# YOTSUBA_AP-ex_EM_ver_3_1.net
KiCad netlist of a schematic drawn in EAGLE
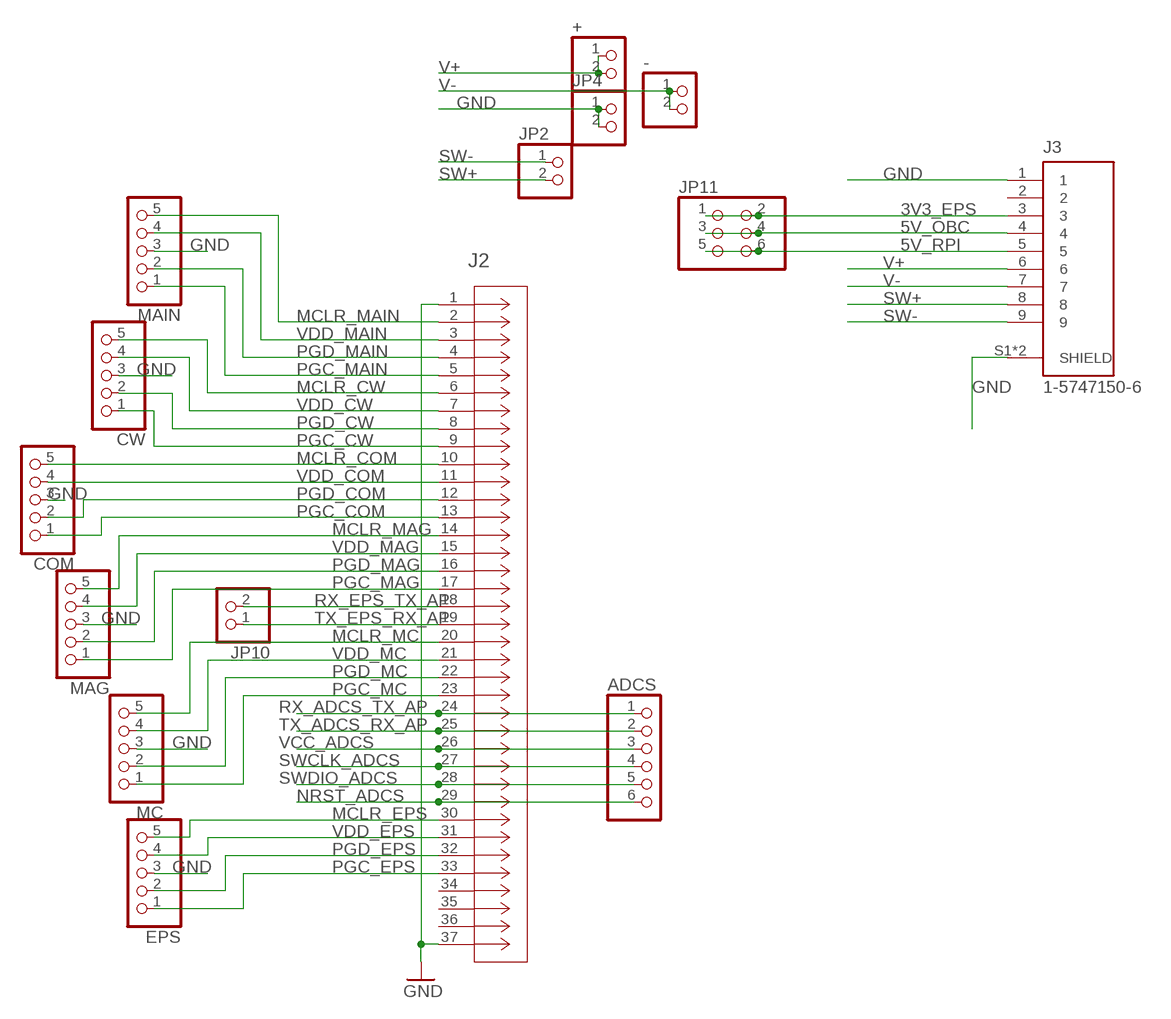
[diagram p0: schematic, sheet 1]

(export (version "E")
  (design (tool "Eeschema 10.0.6"))
  (components
    (comp (ref "+")
      (value "PINHD-1X2")
      (footprint "eagle-import:1X02")
      (libsource (lib "eagle-import") (part "PINHD-1X2"))
    )
    (comp (ref "-")
      (value "PINHD-1X2")
      (footprint "eagle-import:1X02")
      (libsource (lib "eagle-import") (part "PINHD-1X2"))
    )
    (comp (ref "ADCS")
      (value "PINHD-1X6")
      (footprint "eagle-import:1X06")
      (libsource (lib "eagle-import") (part "PINHD-1X6"))
    )
    (comp (ref "COM")
      (value "PINHD-1X5")
      (footprint "eagle-import:1X05")
      (libsource (lib "eagle-import") (part "PINHD-1X5"))
    )
    (comp (ref "CW")
      (value "PINHD-1X5")
      (footprint "eagle-import:1X05")
      (libsource (lib "eagle-import") (part "PINHD-1X5"))
    )
    (comp (ref "EPS")
      (value "PINHD-1X5")
      (footprint "eagle-import:1X05")
      (libsource (lib "eagle-import") (part "PINHD-1X5"))
    )
    (comp (ref "J2")
      (value "1-5747301-6")
      (footprint "eagle-import:CONN_1-5747301-6_TYC")
      (fields (field (name "COPYRIGHT") "Copyright (C) 2023 Ultra Librarian. All rights reserved."))
      (libsource (lib "eagle-import") (part "1-5747301-6"))
    )
    (comp (ref "J3")
      (value "1-5747150-6")
      (footprint "eagle-import:TE_1-5747150-6")
      (fields (field (name "MF") "TE Connectivity"))
      (libsource (lib "eagle-import") (part "1-5747150-6"))
    )
    (comp (ref "JP2")
      (value "PINHD-1X2")
      (footprint "eagle-import:1X02")
      (libsource (lib "eagle-import") (part "PINHD-1X2"))
    )
    (comp (ref "JP4")
      (value "PINHD-1X2")
      (footprint "eagle-import:1X02")
      (libsource (lib "eagle-import") (part "PINHD-1X2"))
    )
    (comp (ref "JP10")
      (value "PINHD-1X2")
      (footprint "eagle-import:1X02")
      (libsource (lib "eagle-import") (part "PINHD-1X2"))
    )
    (comp (ref "JP11")
      (value "PINHD-2X3")
      (footprint "eagle-import:2X03")
      (libsource (lib "eagle-import") (part "PINHD-2X3"))
    )
    (comp (ref "MAG")
      (value "PINHD-1X5")
      (footprint "eagle-import:1X05")
      (libsource (lib "eagle-import") (part "PINHD-1X5"))
    )
    (comp (ref "MAIN")
      (value "PINHD-1X5")
      (footprint "eagle-import:1X05")
      (libsource (lib "eagle-import") (part "PINHD-1X5"))
    )
    (comp (ref "MC")
      (value "PINHD-1X5")
      (footprint "eagle-import:1X05")
      (libsource (lib "eagle-import") (part "PINHD-1X5"))
    )
  )
  (nets
    (net (code "1") (name "/3V3_EPS") (class "Default")
      (node (ref "J3") (pin "3") (pinfunction "3_3") (pintype "passive"))
      (node (ref "JP11") (pin "1") (pinfunction "1_1") (pintype "passive"))
      (node (ref "JP11") (pin "2") (pinfunction "2_2") (pintype "passive"))
    )
    (net (code "2") (name "/5V_OBC") (class "Default")
      (node (ref "J3") (pin "4") (pinfunction "4_4") (pintype "passive"))
      (node (ref "JP11") (pin "3") (pinfunction "3_3") (pintype "passive"))
      (node (ref "JP11") (pin "4") (pinfunction "4_4") (pintype "passive"))
    )
    (net (code "3") (name "/5V_RPI") (class "Default")
      (node (ref "J3") (pin "5") (pinfunction "5_5") (pintype "passive"))
      (node (ref "JP11") (pin "5") (pinfunction "5_5") (pintype "passive"))
      (node (ref "JP11") (pin "6") (pinfunction "6_6") (pintype "passive"))
    )
    (net (code "4") (name "/MCLR_COM") (class "Default")
      (node (ref "COM") (pin "5") (pinfunction "5_5") (pintype "passive"))
      (node (ref "J2") (pin "10") (pinfunction "10_10") (pintype "passive"))
    )
    (net (code "5") (name "/MCLR_CW") (class "Default")
      (node (ref "CW") (pin "5") (pinfunction "5_5") (pintype "passive"))
      (node (ref "J2") (pin "6") (pinfunction "6_6") (pintype "passive"))
    )
    (net (code "6") (name "/MCLR_EPS") (class "Default")
      (node (ref "EPS") (pin "5") (pinfunction "5_5") (pintype "passive"))
      (node (ref "J2") (pin "30") (pinfunction "30_30") (pintype "passive"))
    )
    (net (code "7") (name "/MCLR_MAG") (class "Default")
      (node (ref "J2") (pin "14") (pinfunction "14_14") (pintype "passive"))
      (node (ref "MAG") (pin "5") (pinfunction "5_5") (pintype "passive"))
    )
    (net (code "8") (name "/MCLR_MAIN") (class "Default")
      (node (ref "J2") (pin "2") (pinfunction "2_2") (pintype "passive"))
      (node (ref "MAIN") (pin "5") (pinfunction "5_5") (pintype "passive"))
    )
    (net (code "9") (name "/MCLR_MC") (class "Default")
      (node (ref "J2") (pin "20") (pinfunction "20_20") (pintype "passive"))
      (node (ref "MC") (pin "5") (pinfunction "5_5") (pintype "passive"))
    )
    (net (code "10") (name "/NRST_ADCS") (class "Default")
      (node (ref "ADCS") (pin "6") (pinfunction "6_6") (pintype "passive"))
      (node (ref "J2") (pin "29") (pinfunction "29_29") (pintype "passive"))
    )
    (net (code "11") (name "/PGC_COM") (class "Default")
      (node (ref "COM") (pin "1") (pinfunction "1_1") (pintype "passive"))
      (node (ref "J2") (pin "13") (pinfunction "13_13") (pintype "passive"))
    )
    (net (code "12") (name "/PGC_CW") (class "Default")
      (node (ref "CW") (pin "1") (pinfunction "1_1") (pintype "passive"))
      (node (ref "J2") (pin "9") (pinfunction "9_9") (pintype "passive"))
    )
    (net (code "13") (name "/PGC_EPS") (class "Default")
      (node (ref "EPS") (pin "1") (pinfunction "1_1") (pintype "passive"))
      (node (ref "J2") (pin "33") (pinfunction "33_33") (pintype "passive"))
    )
    (net (code "14") (name "/PGC_MAG") (class "Default")
      (node (ref "J2") (pin "17") (pinfunction "17_17") (pintype "passive"))
      (node (ref "MAG") (pin "1") (pinfunction "1_1") (pintype "passive"))
    )
    (net (code "15") (name "/PGC_MAIN") (class "Default")
      (node (ref "J2") (pin "5") (pinfunction "5_5") (pintype "passive"))
      (node (ref "MAIN") (pin "1") (pinfunction "1_1") (pintype "passive"))
    )
    (net (code "16") (name "/PGC_MC") (class "Default")
      (node (ref "J2") (pin "23") (pinfunction "23_23") (pintype "passive"))
      (node (ref "MC") (pin "1") (pinfunction "1_1") (pintype "passive"))
    )
    (net (code "17") (name "/PGD_COM") (class "Default")
      (node (ref "COM") (pin "2") (pinfunction "2_2") (pintype "passive"))
      (node (ref "J2") (pin "12") (pinfunction "12_12") (pintype "passive"))
    )
    (net (code "18") (name "/PGD_CW") (class "Default")
      (node (ref "CW") (pin "2") (pinfunction "2_2") (pintype "passive"))
      (node (ref "J2") (pin "8") (pinfunction "8_8") (pintype "passive"))
    )
    (net (code "19") (name "/PGD_EPS") (class "Default")
      (node (ref "EPS") (pin "2") (pinfunction "2_2") (pintype "passive"))
      (node (ref "J2") (pin "32") (pinfunction "32_32") (pintype "passive"))
    )
    (net (code "20") (name "/PGD_MAG") (class "Default")
      (node (ref "J2") (pin "16") (pinfunction "16_16") (pintype "passive"))
      (node (ref "MAG") (pin "2") (pinfunction "2_2") (pintype "passive"))
    )
    (net (code "21") (name "/PGD_MAIN") (class "Default")
      (node (ref "J2") (pin "4") (pinfunction "4_4") (pintype "passive"))
      (node (ref "MAIN") (pin "2") (pinfunction "2_2") (pintype "passive"))
    )
    (net (code "22") (name "/PGD_MC") (class "Default")
      (node (ref "J2") (pin "22") (pinfunction "22_22") (pintype "passive"))
      (node (ref "MC") (pin "2") (pinfunction "2_2") (pintype "passive"))
    )
    (net (code "23") (name "/RX_ADCS_TX_AP") (class "Default")
      (node (ref "ADCS") (pin "1") (pinfunction "1_1") (pintype "passive"))
      (node (ref "J2") (pin "24") (pinfunction "24_24") (pintype "passive"))
    )
    (net (code "24") (name "/RX_EPS_TX_AP") (class "Default")
      (node (ref "J2") (pin "18") (pinfunction "18_18") (pintype "passive"))
      (node (ref "JP10") (pin "2") (pinfunction "2_2") (pintype "passive"))
    )
    (net (code "25") (name "/SW+") (class "Default")
      (node (ref "J3") (pin "8") (pinfunction "8_8") (pintype "passive"))
      (node (ref "JP2") (pin "2") (pinfunction "2_2") (pintype "passive"))
    )
    (net (code "26") (name "/SW-") (class "Default")
      (node (ref "J3") (pin "9") (pinfunction "9_9") (pintype "passive"))
      (node (ref "JP2") (pin "1") (pinfunction "1_1") (pintype "passive"))
    )
    (net (code "27") (name "/SWCLK_ADCS") (class "Default")
      (node (ref "ADCS") (pin "4") (pinfunction "4_4") (pintype "passive"))
      (node (ref "J2") (pin "27") (pinfunction "27_27") (pintype "passive"))
    )
    (net (code "28") (name "/SWDIO_ADCS") (class "Default")
      (node (ref "ADCS") (pin "5") (pinfunction "5_5") (pintype "passive"))
      (node (ref "J2") (pin "28") (pinfunction "28_28") (pintype "passive"))
    )
    (net (code "29") (name "/TX_ADCS_RX_AP") (class "Default")
      (node (ref "ADCS") (pin "2") (pinfunction "2_2") (pintype "passive"))
      (node (ref "J2") (pin "25") (pinfunction "25_25") (pintype "passive"))
    )
    (net (code "30") (name "/TX_EPS_RX_AP") (class "Default")
      (node (ref "J2") (pin "19") (pinfunction "19_19") (pintype "passive"))
      (node (ref "JP10") (pin "1") (pinfunction "1_1") (pintype "passive"))
    )
    (net (code "31") (name "/V+") (class "Default")
      (node (ref "+") (pin "1") (pinfunction "1_1") (pintype "passive"))
      (node (ref "+") (pin "2") (pinfunction "2_2") (pintype "passive"))
      (node (ref "J3") (pin "6") (pinfunction "6_6") (pintype "passive"))
    )
    (net (code "32") (name "/V-") (class "Default")
      (node (ref "-") (pin "1") (pinfunction "1_1") (pintype "passive"))
      (node (ref "-") (pin "2") (pinfunction "2_2") (pintype "passive"))
      (node (ref "J3") (pin "7") (pinfunction "7_7") (pintype "passive"))
    )
    (net (code "33") (name "/VCC_ADCS") (class "Default")
      (node (ref "ADCS") (pin "3") (pinfunction "3_3") (pintype "passive"))
      (node (ref "J2") (pin "26") (pinfunction "26_26") (pintype "passive"))
    )
    (net (code "34") (name "/VDD_COM") (class "Default")
      (node (ref "COM") (pin "4") (pinfunction "4_4") (pintype "passive"))
      (node (ref "J2") (pin "11") (pinfunction "11_11") (pintype "passive"))
    )
    (net (code "35") (name "/VDD_CW") (class "Default")
      (node (ref "CW") (pin "4") (pinfunction "4_4") (pintype "passive"))
      (node (ref "J2") (pin "7") (pinfunction "7_7") (pintype "passive"))
    )
    (net (code "36") (name "/VDD_EPS") (class "Default")
      (node (ref "EPS") (pin "4") (pinfunction "4_4") (pintype "passive"))
      (node (ref "J2") (pin "31") (pinfunction "31_31") (pintype "passive"))
    )
    (net (code "37") (name "/VDD_MAG") (class "Default")
      (node (ref "J2") (pin "15") (pinfunction "15_15") (pintype "passive"))
      (node (ref "MAG") (pin "4") (pinfunction "4_4") (pintype "passive"))
    )
    (net (code "38") (name "/VDD_MAIN") (class "Default")
      (node (ref "J2") (pin "3") (pinfunction "3_3") (pintype "passive"))
      (node (ref "MAIN") (pin "4") (pinfunction "4_4") (pintype "passive"))
    )
    (net (code "39") (name "/VDD_MC") (class "Default")
      (node (ref "J2") (pin "21") (pinfunction "21_21") (pintype "passive"))
      (node (ref "MC") (pin "4") (pinfunction "4_4") (pintype "passive"))
    )
    (net (code "40") (name "GND") (class "Default")
      (node (ref "COM") (pin "3") (pinfunction "3_3") (pintype "passive"))
      (node (ref "CW") (pin "3") (pinfunction "3_3") (pintype "passive"))
      (node (ref "EPS") (pin "3") (pinfunction "3_3") (pintype "passive"))
      (node (ref "J2") (pin "1") (pinfunction "1_1") (pintype "passive"))
      (node (ref "J2") (pin "37") (pinfunction "37_37") (pintype "passive"))
      (node (ref "J3") (pin "1") (pinfunction "1_1") (pintype "passive"))
      (node (ref "J3") (pin "S1") (pinfunction "SHIELD_S1") (pintype "passive"))
      (node (ref "J3") (pin "S2") (pinfunction "SHIELD_S2") (pintype "passive"))
      (node (ref "JP4") (pin "1") (pinfunction "1_1") (pintype "passive"))
      (node (ref "JP4") (pin "2") (pinfunction "2_2") (pintype "passive"))
      (node (ref "MAG") (pin "3") (pinfunction "3_3") (pintype "passive"))
      (node (ref "MAIN") (pin "3") (pinfunction "3_3") (pintype "passive"))
      (node (ref "MC") (pin "3") (pinfunction "3_3") (pintype "passive"))
    )
    (net (code "41") (name "unconnected-(J2-Pad34)") (class "Default")
      (node (ref "J2") (pin "34") (pinfunction "34_34") (pintype "passive"))
    )
    (net (code "42") (name "unconnected-(J2-Pad35)") (class "Default")
      (node (ref "J2") (pin "35") (pinfunction "35_35") (pintype "passive"))
    )
    (net (code "43") (name "unconnected-(J2-Pad36)") (class "Default")
      (node (ref "J2") (pin "36") (pinfunction "36_36") (pintype "passive"))
    )
    (net (code "44") (name "unconnected-(J3-Pad2)") (class "Default")
      (node (ref "J3") (pin "2") (pinfunction "2_2") (pintype "passive"))
    )
  )
)
